# MainBoard.net
KiCad netlist of a schematic drawn in EAGLE
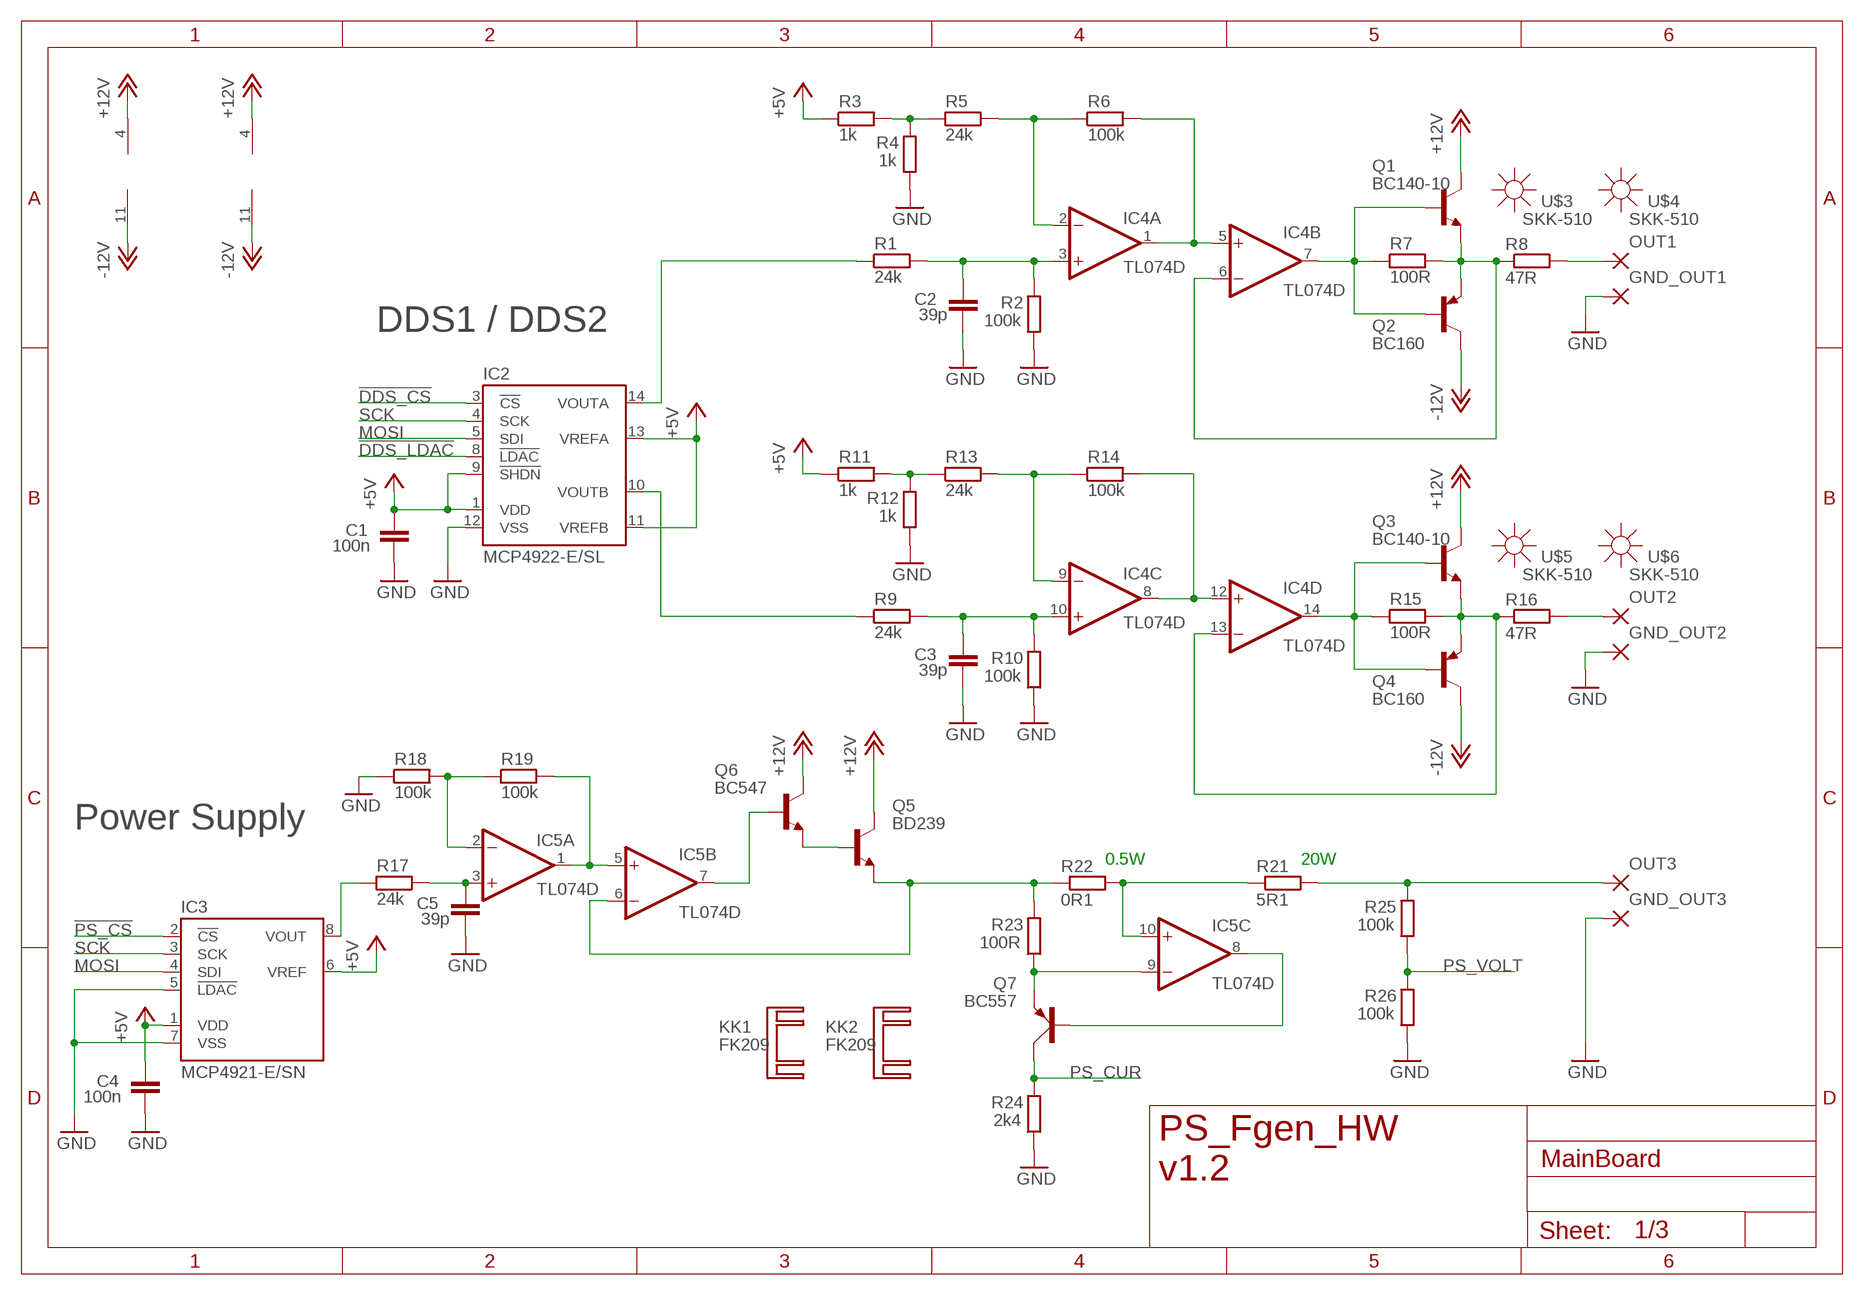
[diagram p0: schematic, sheet 1]
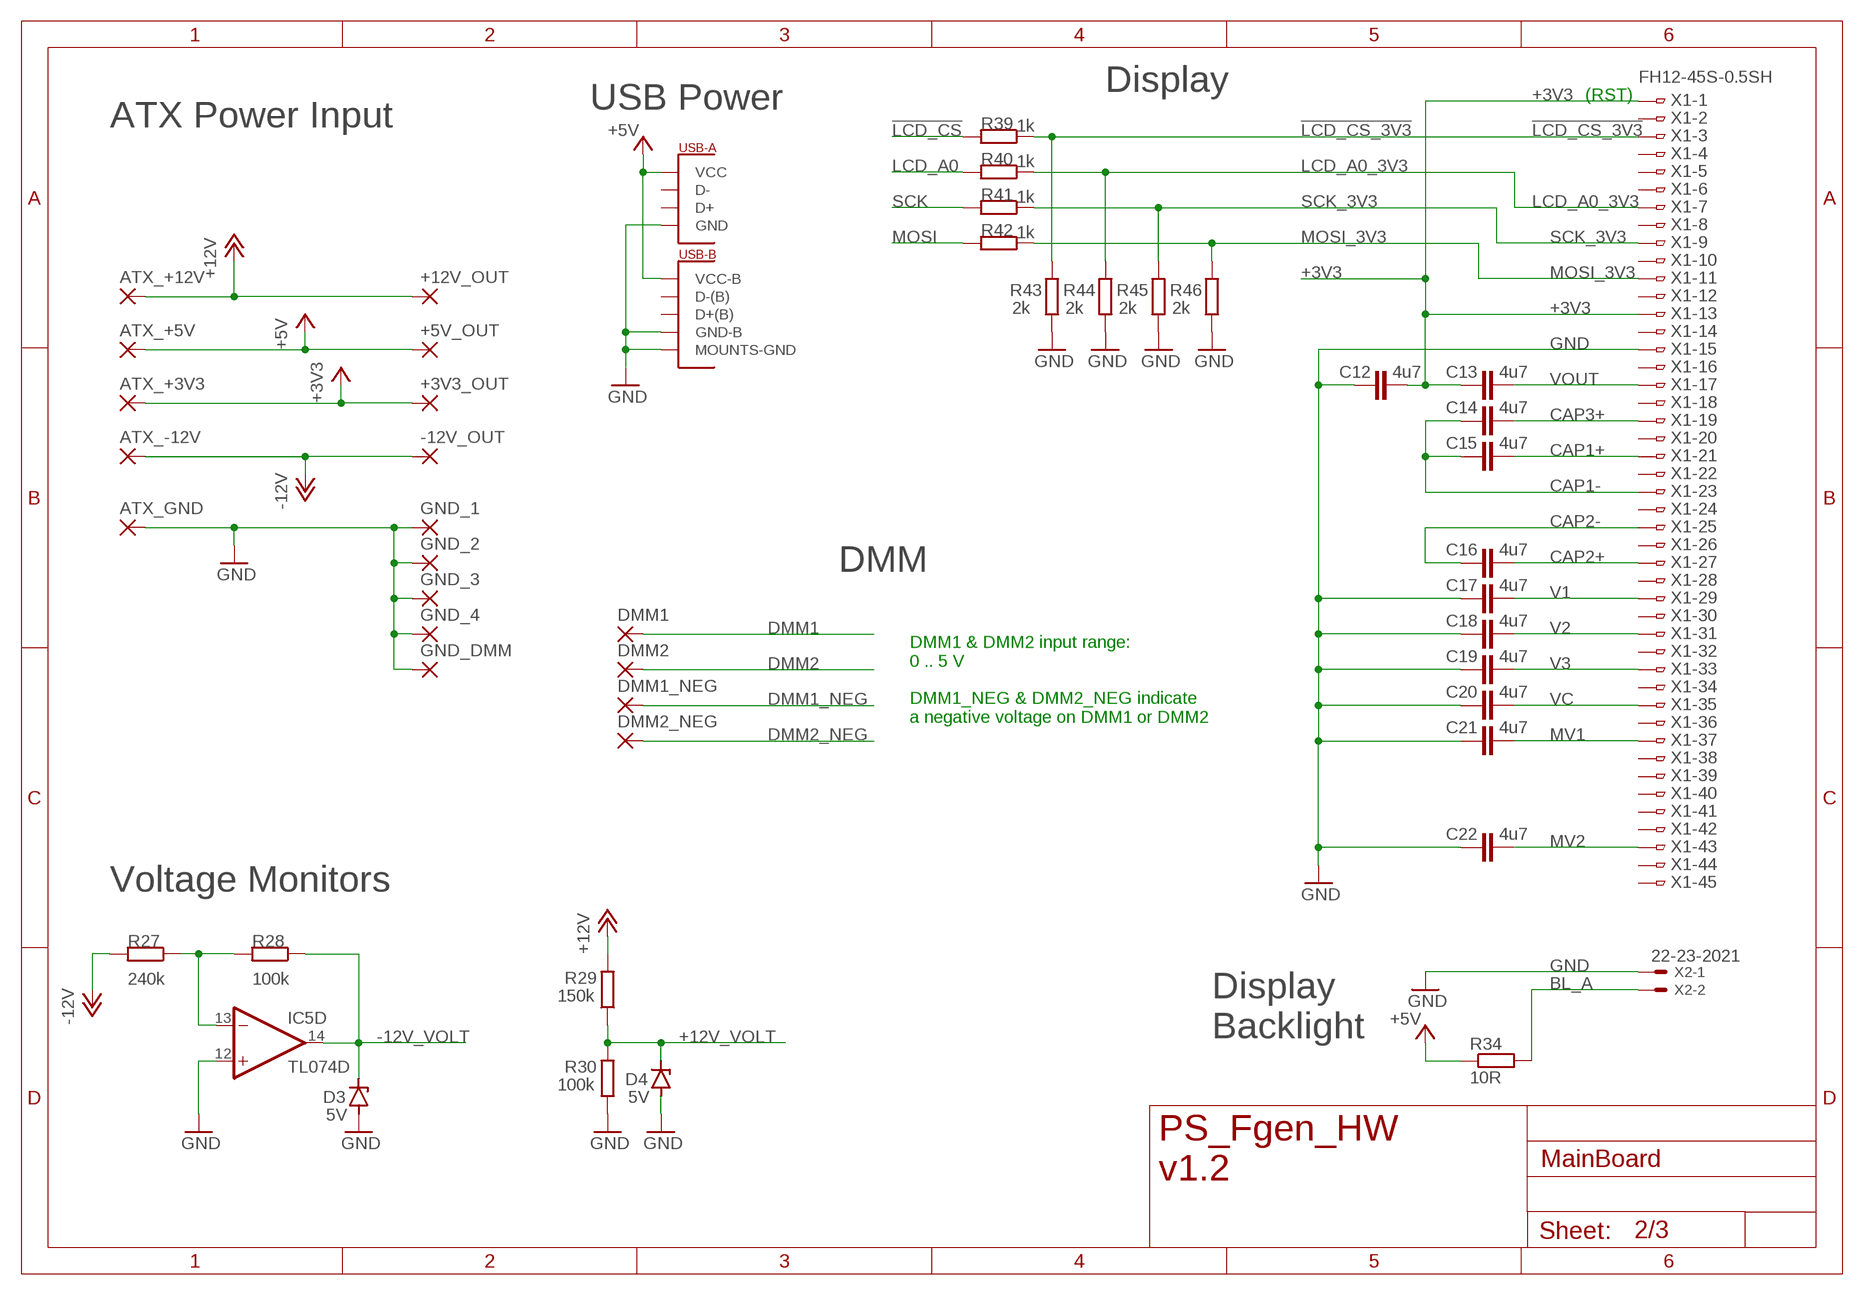
[diagram p1: schematic, sheet 2]
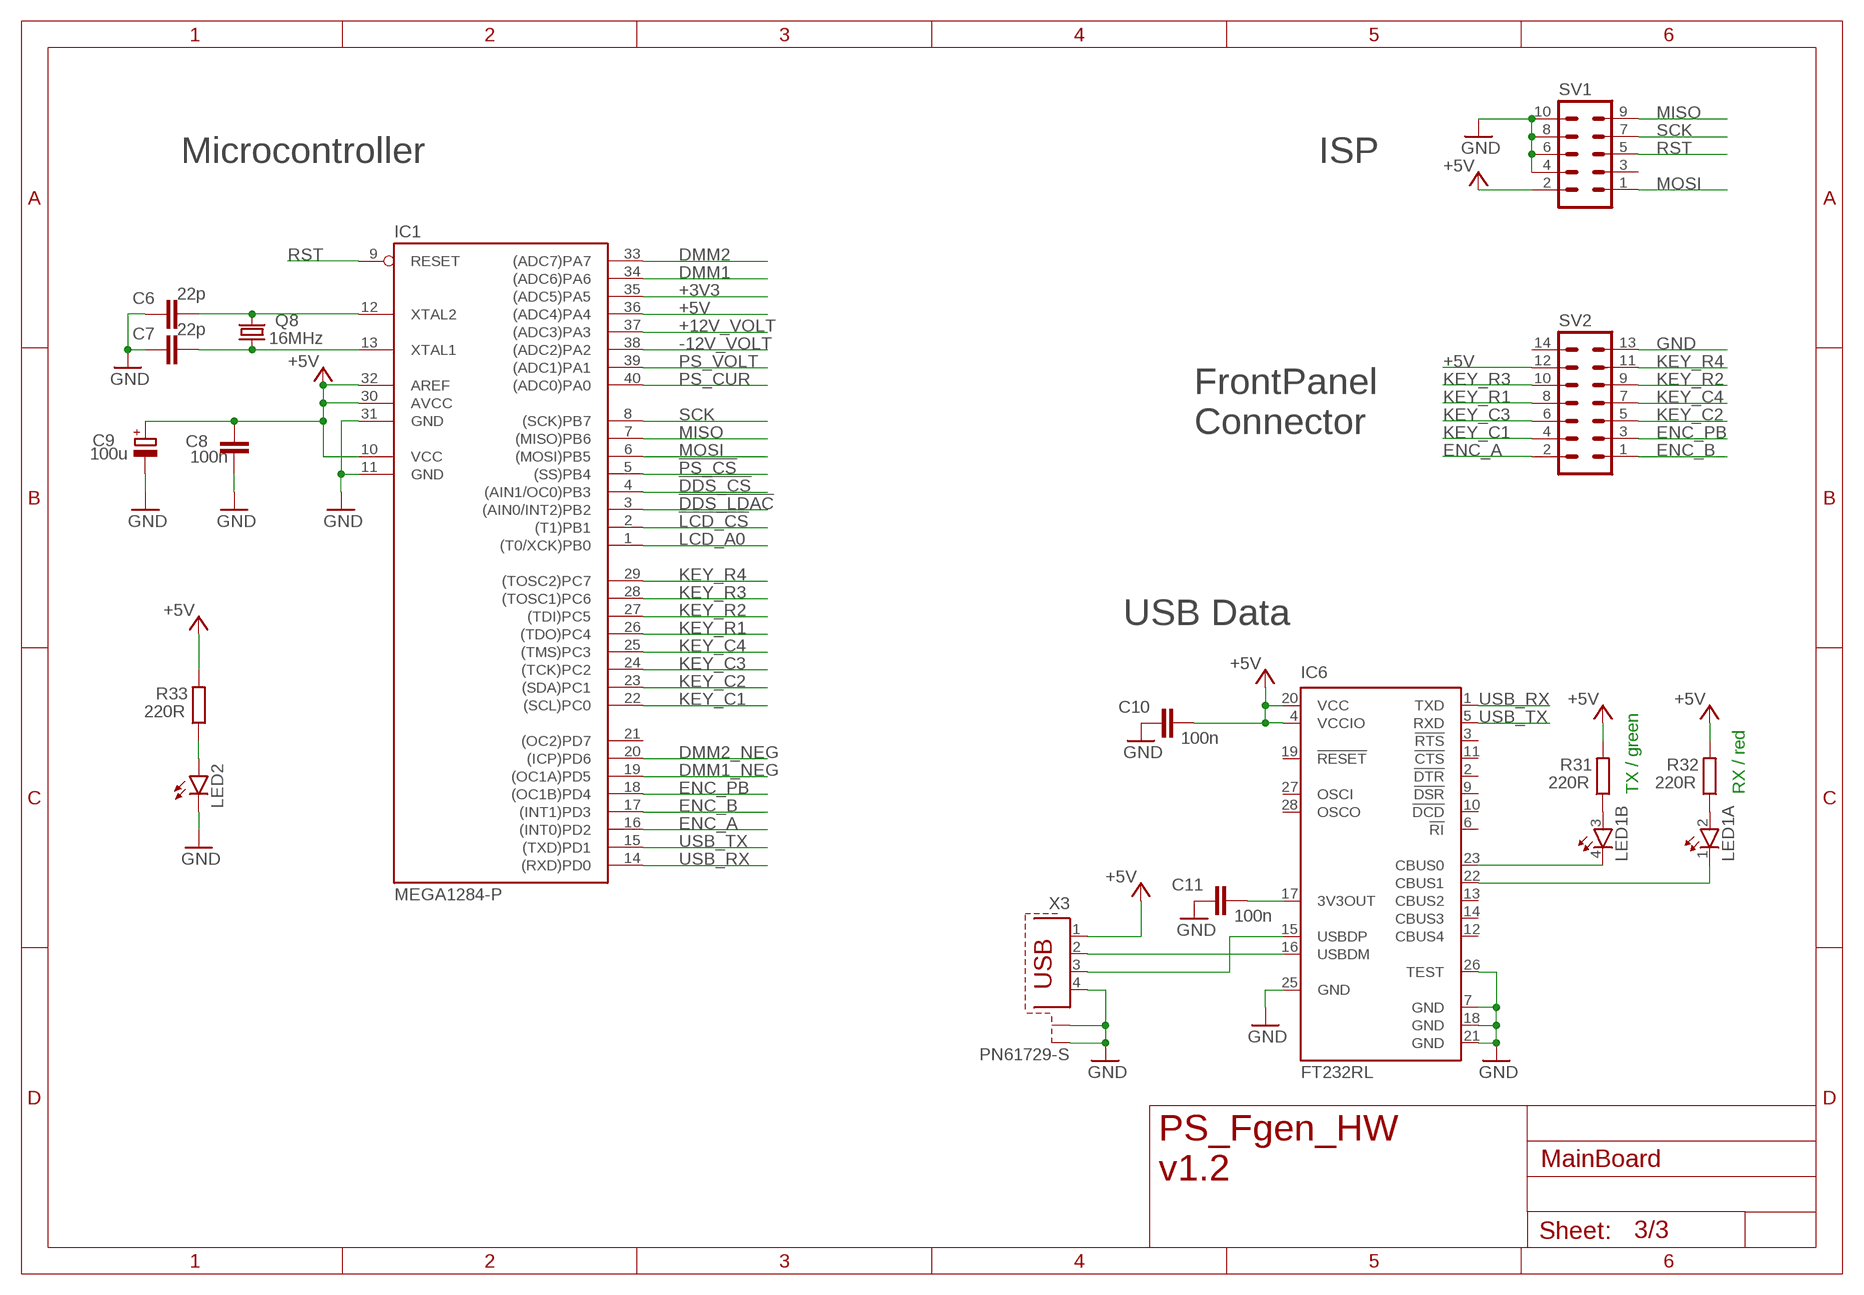
[diagram p2: schematic, sheet 3]

(export (version "E")
  (design (tool "Eeschema 10.0.6"))
  (components
    (comp (ref "C6")
      (value "22p")
      (footprint "eagle-import:C0805")
      (libsource (lib "eagle-import") (part "C-EUC0805"))
    )
    (comp (ref "C7")
      (value "22p")
      (footprint "eagle-import:C0805")
      (libsource (lib "eagle-import") (part "C-EUC0805"))
    )
    (comp (ref "C8")
      (value "100n")
      (footprint "eagle-import:C0805")
      (libsource (lib "eagle-import") (part "C-EUC0805"))
    )
    (comp (ref "C9")
      (value "100u")
      (footprint "eagle-import:PANASONIC_D")
      (libsource (lib "eagle-import") (part "CPOL-EUD"))
    )
    (comp (ref "C10")
      (value "100n")
      (footprint "eagle-import:C0805")
      (libsource (lib "eagle-import") (part "C-EUC0805"))
    )
    (comp (ref "C11")
      (value "100n")
      (footprint "eagle-import:C0805")
      (libsource (lib "eagle-import") (part "C-EUC0805"))
    )
    (comp (ref "IC1")
      (value "MEGA1284-P")
      (footprint "eagle-import:DIL40")
      (fields (field (name "MPN") "ATMEGA16-16PU"))
      (libsource (lib "eagle-import") (part "MEGA16-P"))
    )
    (comp (ref "IC6")
      (value "FT232RL")
      (footprint "eagle-import:SSOP28")
      (libsource (lib "eagle-import") (part "FT232RL"))
    )
    (comp (ref "LED1")
      (value "TOPLED-2--")
      (footprint "eagle-import:P-LCC-4-2")
      (libsource (lib "eagle-import") (part "TOPLED-2--"))
    )
    (comp (ref "LED2")
      (value "LEDCHIP-LED0805")
      (footprint "eagle-import:CHIP-LED0805")
      (libsource (lib "eagle-import") (part "LEDCHIP-LED0805"))
    )
    (comp (ref "Q8")
      (value "16MHz")
      (footprint "eagle-import:HC49_S")
      (libsource (lib "eagle-import") (part "CRYSTALHC49S"))
    )
    (comp (ref "R31")
      (value "220R")
      (footprint "eagle-import:R0805")
      (libsource (lib "eagle-import") (part "R-EU_R0805"))
    )
    (comp (ref "R32")
      (value "220R")
      (footprint "eagle-import:R0805")
      (libsource (lib "eagle-import") (part "R-EU_R0805"))
    )
    (comp (ref "R33")
      (value "220R")
      (footprint "eagle-import:R0805")
      (libsource (lib "eagle-import") (part "R-EU_R0805"))
    )
    (comp (ref "SV1")
      (value "ML10")
      (footprint "eagle-import:ML10")
      (libsource (lib "eagle-import") (part "ML10"))
    )
    (comp (ref "SV2")
      (value "ML14")
      (footprint "eagle-import:ML14")
      (libsource (lib "eagle-import") (part "ML14"))
    )
    (comp (ref "X3")
      (value "PN61729-S")
      (footprint "eagle-import:PN61729-S")
      (libsource (lib "eagle-import") (part "PN61729-S"))
    )
    (comp (ref "C1")
      (value "100n")
      (footprint "eagle-import:C0805")
      (libsource (lib "eagle-import") (part "C-EUC0805"))
    )
    (comp (ref "C2")
      (value "39p")
      (footprint "eagle-import:C0805")
      (libsource (lib "eagle-import") (part "C-EUC0805"))
    )
    (comp (ref "C3")
      (value "39p")
      (footprint "eagle-import:C0805")
      (libsource (lib "eagle-import") (part "C-EUC0805"))
    )
    (comp (ref "C4")
      (value "100n")
      (footprint "eagle-import:C0805")
      (libsource (lib "eagle-import") (part "C-EUC0805"))
    )
    (comp (ref "C5")
      (value "39p")
      (footprint "eagle-import:C0805")
      (libsource (lib "eagle-import") (part "C-EUC0805"))
    )
    (comp (ref "GND_OUT1")
      (value "2,54/1,0")
      (footprint "eagle-import:2,54_1,0")
      (libsource (lib "eagle-import") (part "2,54/1,0"))
    )
    (comp (ref "GND_OUT2")
      (value "2,54/1,0")
      (footprint "eagle-import:2,54_1,0")
      (libsource (lib "eagle-import") (part "2,54/1,0"))
    )
    (comp (ref "GND_OUT3")
      (value "2,54/1,0")
      (footprint "eagle-import:2,54_1,0")
      (libsource (lib "eagle-import") (part "2,54/1,0"))
    )
    (comp (ref "IC2")
      (value "MCP4922-E/SL")
      (footprint "eagle-import:SO14")
      (libsource (lib "eagle-import") (part "MCP4922-E/SL"))
    )
    (comp (ref "IC3")
      (value "MCP4921-E/SN")
      (footprint "eagle-import:SO08")
      (libsource (lib "eagle-import") (part "MCP4921-E/SN"))
    )
    (comp (ref "IC4")
      (value "TL074D")
      (footprint "eagle-import:SO14")
      (libsource (lib "eagle-import") (part "TL074D"))
    )
    (comp (ref "IC5")
      (value "TL074D")
      (footprint "eagle-import:SO14")
      (libsource (lib "eagle-import") (part "TL074D"))
    )
    (comp (ref "KK1")
      (value "FK209")
      (footprint "eagle-import:FK209")
      (libsource (lib "eagle-import") (part "FK209"))
    )
    (comp (ref "KK2")
      (value "FK209")
      (footprint "eagle-import:FK209")
      (libsource (lib "eagle-import") (part "FK209"))
    )
    (comp (ref "OUT1")
      (value "2,54/1,0")
      (footprint "eagle-import:2,54_1,0")
      (libsource (lib "eagle-import") (part "2,54/1,0"))
    )
    (comp (ref "OUT2")
      (value "2,54/1,0")
      (footprint "eagle-import:2,54_1,0")
      (libsource (lib "eagle-import") (part "2,54/1,0"))
    )
    (comp (ref "OUT3")
      (value "2,54/1,0")
      (footprint "eagle-import:2,54_1,0")
      (libsource (lib "eagle-import") (part "2,54/1,0"))
    )
    (comp (ref "Q1")
      (value "BC140-10")
      (footprint "eagle-import:TO39")
      (libsource (lib "eagle-import") (part "BC140-10"))
    )
    (comp (ref "Q2")
      (value "BC160")
      (footprint "eagle-import:TO39")
      (libsource (lib "eagle-import") (part "BC160"))
    )
    (comp (ref "Q3")
      (value "BC140-10")
      (footprint "eagle-import:TO39")
      (libsource (lib "eagle-import") (part "BC140-10"))
    )
    (comp (ref "Q4")
      (value "BC160")
      (footprint "eagle-import:TO39")
      (libsource (lib "eagle-import") (part "BC160"))
    )
    (comp (ref "Q5")
      (value "BD239")
      (footprint "eagle-import:CB-274")
      (libsource (lib "eagle-import") (part "BD239TO220BV"))
    )
    (comp (ref "Q6")
      (value "BC547")
      (footprint "eagle-import:TO92")
      (libsource (lib "eagle-import") (part "BC547"))
    )
    (comp (ref "Q7")
      (value "BC557")
      (footprint "eagle-import:SOT54A")
      (libsource (lib "eagle-import") (part "BC557"))
    )
    (comp (ref "R1")
      (value "24k")
      (footprint "eagle-import:R0805")
      (libsource (lib "eagle-import") (part "R-EU_R0805"))
    )
    (comp (ref "R2")
      (value "100k")
      (footprint "eagle-import:R0805")
      (libsource (lib "eagle-import") (part "R-EU_R0805"))
    )
    (comp (ref "R3")
      (value "1k")
      (footprint "eagle-import:R0805")
      (libsource (lib "eagle-import") (part "R-EU_R0805"))
    )
    (comp (ref "R4")
      (value "1k")
      (footprint "eagle-import:R0805")
      (libsource (lib "eagle-import") (part "R-EU_R0805"))
    )
    (comp (ref "R5")
      (value "24k")
      (footprint "eagle-import:R0805")
      (libsource (lib "eagle-import") (part "R-EU_R0805"))
    )
    (comp (ref "R6")
      (value "100k")
      (footprint "eagle-import:R0805")
      (libsource (lib "eagle-import") (part "R-EU_R0805"))
    )
    (comp (ref "R7")
      (value "100R")
      (footprint "eagle-import:R0805")
      (libsource (lib "eagle-import") (part "R-EU_R0805"))
    )
    (comp (ref "R8")
      (value "47R")
      (footprint "eagle-import:0411_15")
      (libsource (lib "eagle-import") (part "R-EU_0411/15"))
    )
    (comp (ref "R9")
      (value "24k")
      (footprint "eagle-import:R0805")
      (libsource (lib "eagle-import") (part "R-EU_R0805"))
    )
    (comp (ref "R10")
      (value "100k")
      (footprint "eagle-import:R0805")
      (libsource (lib "eagle-import") (part "R-EU_R0805"))
    )
    (comp (ref "R11")
      (value "1k")
      (footprint "eagle-import:R0805")
      (libsource (lib "eagle-import") (part "R-EU_R0805"))
    )
    (comp (ref "R12")
      (value "1k")
      (footprint "eagle-import:R0805")
      (libsource (lib "eagle-import") (part "R-EU_R0805"))
    )
    (comp (ref "R13")
      (value "24k")
      (footprint "eagle-import:R0805")
      (libsource (lib "eagle-import") (part "R-EU_R0805"))
    )
    (comp (ref "R14")
      (value "100k")
      (footprint "eagle-import:R0805")
      (libsource (lib "eagle-import") (part "R-EU_R0805"))
    )
    (comp (ref "R15")
      (value "100R")
      (footprint "eagle-import:R0805")
      (libsource (lib "eagle-import") (part "R-EU_R0805"))
    )
    (comp (ref "R16")
      (value "47R")
      (footprint "eagle-import:0411_15")
      (libsource (lib "eagle-import") (part "R-EU_0411/15"))
    )
    (comp (ref "R17")
      (value "24k")
      (footprint "eagle-import:R0805")
      (libsource (lib "eagle-import") (part "R-EU_R0805"))
    )
    (comp (ref "R18")
      (value "100k")
      (footprint "eagle-import:R0805")
      (libsource (lib "eagle-import") (part "R-EU_R0805"))
    )
    (comp (ref "R19")
      (value "100k")
      (footprint "eagle-import:R0805")
      (libsource (lib "eagle-import") (part "R-EU_R0805"))
    )
    (comp (ref "R21")
      (value "5R1")
      (footprint "eagle-import:0411_15")
      (libsource (lib "eagle-import") (part "R-EU_0411/15"))
    )
    (comp (ref "R22")
      (value "0R1")
      (footprint "eagle-import:0411_15")
      (libsource (lib "eagle-import") (part "R-EU_0411/15"))
    )
    (comp (ref "R23")
      (value "100R")
      (footprint "eagle-import:R0805")
      (libsource (lib "eagle-import") (part "R-EU_R0805"))
    )
    (comp (ref "R24")
      (value "2k4")
      (footprint "eagle-import:R0805")
      (libsource (lib "eagle-import") (part "R-EU_R0805"))
    )
    (comp (ref "R25")
      (value "100k")
      (footprint "eagle-import:R0805")
      (libsource (lib "eagle-import") (part "R-EU_R0805"))
    )
    (comp (ref "R26")
      (value "100k")
      (footprint "eagle-import:R0805")
      (libsource (lib "eagle-import") (part "R-EU_R0805"))
    )
    (comp (ref "U$3")
      (value "SKK-510")
      (footprint "eagle-import:SKK")
      (libsource (lib "eagle-import") (part "SKK-510"))
    )
    (comp (ref "U$4")
      (value "SKK-510")
      (footprint "eagle-import:SKK")
      (libsource (lib "eagle-import") (part "SKK-510"))
    )
    (comp (ref "U$5")
      (value "SKK-510")
      (footprint "eagle-import:SKK")
      (libsource (lib "eagle-import") (part "SKK-510"))
    )
    (comp (ref "U$6")
      (value "SKK-510")
      (footprint "eagle-import:SKK")
      (libsource (lib "eagle-import") (part "SKK-510"))
    )
    (comp (ref "+3V3_OUT")
      (value "2,54/1,0")
      (footprint "eagle-import:2,54_1,0")
      (libsource (lib "eagle-import") (part "2,54/1,0"))
    )
    (comp (ref "+5V_OUT")
      (value "2,54/1,0")
      (footprint "eagle-import:2,54_1,0")
      (libsource (lib "eagle-import") (part "2,54/1,0"))
    )
    (comp (ref "+12V_OUT")
      (value "2,54/1,0")
      (footprint "eagle-import:2,54_1,0")
      (libsource (lib "eagle-import") (part "2,54/1,0"))
    )
    (comp (ref "-12V_OUT")
      (value "2,54/1,0")
      (footprint "eagle-import:2,54_1,0")
      (libsource (lib "eagle-import") (part "2,54/1,0"))
    )
    (comp (ref "ATX_+3V3")
      (value "2,54/1,0")
      (footprint "eagle-import:2,54_1,0")
      (libsource (lib "eagle-import") (part "2,54/1,0"))
    )
    (comp (ref "ATX_+5V")
      (value "2,54/1,0")
      (footprint "eagle-import:2,54_1,0")
      (libsource (lib "eagle-import") (part "2,54/1,0"))
    )
    (comp (ref "ATX_+12V")
      (value "2,54/1,0")
      (footprint "eagle-import:2,54_1,0")
      (libsource (lib "eagle-import") (part "2,54/1,0"))
    )
    (comp (ref "ATX_-12V")
      (value "2,54/1,0")
      (footprint "eagle-import:2,54_1,0")
      (libsource (lib "eagle-import") (part "2,54/1,0"))
    )
    (comp (ref "ATX_GND")
      (value "2,54/1,0")
      (footprint "eagle-import:2,54_1,0")
      (libsource (lib "eagle-import") (part "2,54/1,0"))
    )
    (comp (ref "C12")
      (value "4u7")
      (footprint "eagle-import:C0805")
      (libsource (lib "eagle-import") (part "C-EUC0805"))
    )
    (comp (ref "C13")
      (value "4u7")
      (footprint "eagle-import:C0805")
      (libsource (lib "eagle-import") (part "C-EUC0805"))
    )
    (comp (ref "C14")
      (value "4u7")
      (footprint "eagle-import:C0805")
      (libsource (lib "eagle-import") (part "C-EUC0805"))
    )
    (comp (ref "C15")
      (value "4u7")
      (footprint "eagle-import:C0805")
      (libsource (lib "eagle-import") (part "C-EUC0805"))
    )
    (comp (ref "C16")
      (value "4u7")
      (footprint "eagle-import:C0805")
      (libsource (lib "eagle-import") (part "C-EUC0805"))
    )
    (comp (ref "C17")
      (value "4u7")
      (footprint "eagle-import:C0805")
      (libsource (lib "eagle-import") (part "C-EUC0805"))
    )
    (comp (ref "C18")
      (value "4u7")
      (footprint "eagle-import:C0805")
      (libsource (lib "eagle-import") (part "C-EUC0805"))
    )
    (comp (ref "C19")
      (value "4u7")
      (footprint "eagle-import:C0805")
      (libsource (lib "eagle-import") (part "C-EUC0805"))
    )
    (comp (ref "C20")
      (value "4u7")
      (footprint "eagle-import:C0805")
      (libsource (lib "eagle-import") (part "C-EUC0805"))
    )
    (comp (ref "C21")
      (value "4u7")
      (footprint "eagle-import:C0805")
      (libsource (lib "eagle-import") (part "C-EUC0805"))
    )
    (comp (ref "C22")
      (value "4u7")
      (footprint "eagle-import:C0805")
      (libsource (lib "eagle-import") (part "C-EUC0805"))
    )
    (comp (ref "D3")
      (value "5V")
      (footprint "eagle-import:SOD80C")
      (libsource (lib "eagle-import") (part "ZENER-DIODESOD80C"))
    )
    (comp (ref "D4")
      (value "5V")
      (footprint "eagle-import:SOD80C")
      (libsource (lib "eagle-import") (part "ZENER-DIODESOD80C"))
    )
    (comp (ref "DMM1")
      (value "2,54/1,0")
      (footprint "eagle-import:2,54_1,0")
      (libsource (lib "eagle-import") (part "2,54/1,0"))
    )
    (comp (ref "DMM1_NEG")
      (value "2,54/1,0")
      (footprint "eagle-import:2,54_1,0")
      (libsource (lib "eagle-import") (part "2,54/1,0"))
    )
    (comp (ref "DMM2")
      (value "2,54/1,0")
      (footprint "eagle-import:2,54_1,0")
      (libsource (lib "eagle-import") (part "2,54/1,0"))
    )
    (comp (ref "DMM2_NEG")
      (value "2,54/1,0")
      (footprint "eagle-import:2,54_1,0")
      (libsource (lib "eagle-import") (part "2,54/1,0"))
    )
    (comp (ref "GND_1")
      (value "2,54/1,0")
      (footprint "eagle-import:2,54_1,0")
      (libsource (lib "eagle-import") (part "2,54/1,0"))
    )
    (comp (ref "GND_2")
      (value "2,54/1,0")
      (footprint "eagle-import:2,54_1,0")
      (libsource (lib "eagle-import") (part "2,54/1,0"))
    )
    (comp (ref "GND_3")
      (value "2,54/1,0")
      (footprint "eagle-import:2,54_1,0")
      (libsource (lib "eagle-import") (part "2,54/1,0"))
    )
    (comp (ref "GND_4")
      (value "2,54/1,0")
      (footprint "eagle-import:2,54_1,0")
      (libsource (lib "eagle-import") (part "2,54/1,0"))
    )
    (comp (ref "GND_DMM")
      (value "2,54/1,0")
      (footprint "eagle-import:2,54_1,0")
      (libsource (lib "eagle-import") (part "2,54/1,0"))
    )
    (comp (ref "R27")
      (value "240k")
      (footprint "eagle-import:R0805")
      (libsource (lib "eagle-import") (part "R-EU_R0805"))
    )
    (comp (ref "R28")
      (value "100k")
      (footprint "eagle-import:R0805")
      (libsource (lib "eagle-import") (part "R-EU_R0805"))
    )
    (comp (ref "R29")
      (value "150k")
      (footprint "eagle-import:R0805")
      (libsource (lib "eagle-import") (part "R-EU_R0805"))
    )
    (comp (ref "R30")
      (value "100k")
      (footprint "eagle-import:R0805")
      (libsource (lib "eagle-import") (part "R-EU_R0805"))
    )
    (comp (ref "R34")
      (value "10R")
      (footprint "eagle-import:R0805")
      (libsource (lib "eagle-import") (part "rcl_334_R-EU_R0805"))
    )
    (comp (ref "R39")
      (value "1k")
      (footprint "eagle-import:R0805")
      (libsource (lib "eagle-import") (part "R-EU_R0805"))
    )
    (comp (ref "R40")
      (value "1k")
      (footprint "eagle-import:R0805")
      (libsource (lib "eagle-import") (part "R-EU_R0805"))
    )
    (comp (ref "R41")
      (value "1k")
      (footprint "eagle-import:R0805")
      (libsource (lib "eagle-import") (part "R-EU_R0805"))
    )
    (comp (ref "R42")
      (value "1k")
      (footprint "eagle-import:R0805")
      (libsource (lib "eagle-import") (part "R-EU_R0805"))
    )
    (comp (ref "R43")
      (value "2k")
      (footprint "eagle-import:R0805")
      (libsource (lib "eagle-import") (part "R-EU_R0805"))
    )
    (comp (ref "R44")
      (value "2k")
      (footprint "eagle-import:R0805")
      (libsource (lib "eagle-import") (part "R-EU_R0805"))
    )
    (comp (ref "R45")
      (value "2k")
      (footprint "eagle-import:R0805")
      (libsource (lib "eagle-import") (part "R-EU_R0805"))
    )
    (comp (ref "R46")
      (value "2k")
      (footprint "eagle-import:R0805")
      (libsource (lib "eagle-import") (part "R-EU_R0805"))
    )
    (comp (ref "U$2")
      (value "DUAL-PORT-USB-REC")
      (footprint "eagle-import:DUAL-PORT-USB")
      (libsource (lib "eagle-import") (part "DUAL-PORT-USB-REC"))
    )
    (comp (ref "X1")
      (value "FH12-45S-0.5SH")
      (footprint "eagle-import:FH12-45S-0.5SH")
      (libsource (lib "eagle-import") (part "FH12-45S-0.5SH"))
    )
    (comp (ref "X2")
      (value "22-23-2021")
      (footprint "eagle-import:22-23-2021")
      (fields (field (name "MF") "MOLEX"))
      (libsource (lib "eagle-import") (part "22-23-2021"))
    )
  )
  (nets
    (net (code "1") (name "+3V3") (class "Default")
      (node (ref "+3V3_OUT") (pin "1") (pinfunction "P_1") (pintype "passive"))
      (node (ref "ATX_+3V3") (pin "1") (pinfunction "P_1") (pintype "passive"))
      (node (ref "C12") (pin "1") (pinfunction "1_1") (pintype "passive"))
      (node (ref "C13") (pin "2") (pinfunction "2_2") (pintype "passive"))
      (node (ref "IC1") (pin "35") (pinfunction "(ADC5)PA5_35") (pintype "bidirectional"))
      (node (ref "X1") (pin "1") (pinfunction "1_1") (pintype "passive"))
      (node (ref "X1") (pin "13") (pinfunction "1_13") (pintype "passive"))
    )
    (net (code "2") (name "+5V") (class "Default")
      (node (ref "+5V_OUT") (pin "1") (pinfunction "P_1") (pintype "passive"))
      (node (ref "ATX_+5V") (pin "1") (pinfunction "P_1") (pintype "passive"))
      (node (ref "C1") (pin "2") (pinfunction "2_2") (pintype "passive"))
      (node (ref "C10") (pin "1") (pinfunction "1_1") (pintype "passive"))
      (node (ref "C4") (pin "2") (pinfunction "2_2") (pintype "passive"))
      (node (ref "C8") (pin "2") (pinfunction "2_2") (pintype "passive"))
      (node (ref "C9") (pin "+") (pinfunction "+_+") (pintype "passive"))
      (node (ref "IC1") (pin "10") (pinfunction "VCC_10") (pintype "power_in"))
      (node (ref "IC1") (pin "30") (pinfunction "AVCC_30") (pintype "power_in"))
      (node (ref "IC1") (pin "32") (pinfunction "AREF_32") (pintype "passive"))
      (node (ref "IC1") (pin "36") (pinfunction "(ADC4)PA4_36") (pintype "bidirectional"))
      (node (ref "IC2") (pin "1") (pinfunction "VDD_1") (pintype "power_in"))
      (node (ref "IC2") (pin "11") (pinfunction "VREFB_11") (pintype "input"))
      (node (ref "IC2") (pin "13") (pinfunction "VREFA_13") (pintype "input"))
      (node (ref "IC2") (pin "9") (pinfunction "~{SHDN}_9") (pintype "input"))
      (node (ref "IC3") (pin "1") (pinfunction "VDD_1") (pintype "power_in"))
      (node (ref "IC3") (pin "6") (pinfunction "VREF_6") (pintype "input"))
      (node (ref "IC6") (pin "20") (pinfunction "VCC_20") (pintype "power_in"))
      (node (ref "IC6") (pin "4") (pinfunction "VCCIO_4") (pintype "power_in"))
      (node (ref "R11") (pin "1") (pinfunction "1_1") (pintype "passive"))
      (node (ref "R3") (pin "1") (pinfunction "1_1") (pintype "passive"))
      (node (ref "R31") (pin "2") (pinfunction "2_2") (pintype "passive"))
      (node (ref "R32") (pin "2") (pinfunction "2_2") (pintype "passive"))
      (node (ref "R33") (pin "2") (pinfunction "2_2") (pintype "passive"))
      (node (ref "R34") (pin "1") (pinfunction "1_1") (pintype "passive"))
      (node (ref "SV1") (pin "2") (pinfunction "2_2") (pintype "passive"))
      (node (ref "SV2") (pin "12") (pinfunction "12_12") (pintype "passive"))
      (node (ref "U$2") (pin "P$10") (pinfunction "VCC-B_P$10") (pintype "power_in"))
      (node (ref "U$2") (pin "P$12") (pinfunction "VCC_P$12") (pintype "power_in"))
      (node (ref "X3") (pin "1") (pinfunction "1_1") (pintype "passive"))
    )
    (net (code "3") (name "+12V") (class "Default")
      (node (ref "+12V_OUT") (pin "1") (pinfunction "P_1") (pintype "passive"))
      (node (ref "ATX_+12V") (pin "1") (pinfunction "P_1") (pintype "passive"))
      (node (ref "IC4") (pin "4") (pinfunction "V+_4") (pintype "power_in"))
      (node (ref "IC5") (pin "4") (pinfunction "V+_4") (pintype "power_in"))
      (node (ref "Q1") (pin "3") (pinfunction "C_3") (pintype "passive"))
      (node (ref "Q3") (pin "3") (pinfunction "C_3") (pintype "passive"))
      (node (ref "Q5") (pin "T2") (pinfunction "C_T2") (pintype "passive"))
      (node (ref "Q6") (pin "3") (pinfunction "C_3") (pintype "passive"))
      (node (ref "R29") (pin "2") (pinfunction "2_2") (pintype "passive"))
    )
    (net (code "4") (name "+12V_VOLT") (class "Default")
      (node (ref "D4") (pin "C") (pinfunction "C_C") (pintype "passive"))
      (node (ref "IC1") (pin "37") (pinfunction "(ADC3)PA3_37") (pintype "bidirectional"))
      (node (ref "R29") (pin "1") (pinfunction "1_1") (pintype "passive"))
      (node (ref "R30") (pin "2") (pinfunction "2_2") (pintype "passive"))
    )
    (net (code "5") (name "-12V") (class "Default")
      (node (ref "-12V_OUT") (pin "1") (pinfunction "P_1") (pintype "passive"))
      (node (ref "ATX_-12V") (pin "1") (pinfunction "P_1") (pintype "passive"))
      (node (ref "IC4") (pin "11") (pinfunction "V-_11") (pintype "power_in"))
      (node (ref "IC5") (pin "11") (pinfunction "V-_11") (pintype "power_in"))
      (node (ref "Q2") (pin "3") (pinfunction "C_3") (pintype "passive"))
      (node (ref "Q4") (pin "3") (pinfunction "C_3") (pintype "passive"))
      (node (ref "R27") (pin "2") (pinfunction "2_2") (pintype "passive"))
    )
    (net (code "6") (name "-12V_VOLT") (class "Default")
      (node (ref "D3") (pin "C") (pinfunction "C_C") (pintype "passive"))
      (node (ref "IC1") (pin "38") (pinfunction "(ADC2)PA2_38") (pintype "bidirectional"))
      (node (ref "IC5") (pin "14") (pinfunction "OUT_14") (pintype "output"))
      (node (ref "R28") (pin "1") (pinfunction "1_1") (pintype "passive"))
    )
    (net (code "7") (name "BL_A") (class "Default")
      (node (ref "R34") (pin "2") (pinfunction "2_2") (pintype "passive"))
      (node (ref "X2") (pin "2") (pinfunction "S_2") (pintype "passive"))
    )
    (net (code "8") (name "CAP1+") (class "Default")
      (node (ref "C15") (pin "1") (pinfunction "1_1") (pintype "passive"))
      (node (ref "X1") (pin "21") (pinfunction "1_21") (pintype "passive"))
    )
    (net (code "9") (name "CAP1-") (class "Default")
      (node (ref "C14") (pin "2") (pinfunction "2_2") (pintype "passive"))
      (node (ref "C15") (pin "2") (pinfunction "2_2") (pintype "passive"))
      (node (ref "X1") (pin "23") (pinfunction "1_23") (pintype "passive"))
    )
    (net (code "10") (name "CAP2+") (class "Default")
      (node (ref "C16") (pin "1") (pinfunction "1_1") (pintype "passive"))
      (node (ref "X1") (pin "27") (pinfunction "1_27") (pintype "passive"))
    )
    (net (code "11") (name "CAP2-") (class "Default")
      (node (ref "C16") (pin "2") (pinfunction "2_2") (pintype "passive"))
      (node (ref "X1") (pin "25") (pinfunction "1_25") (pintype "passive"))
    )
    (net (code "12") (name "CAP3+") (class "Default")
      (node (ref "C14") (pin "1") (pinfunction "1_1") (pintype "passive"))
      (node (ref "X1") (pin "19") (pinfunction "1_19") (pintype "passive"))
    )
    (net (code "13") (name "DMM1") (class "Default")
      (node (ref "DMM1") (pin "1") (pinfunction "P_1") (pintype "passive"))
      (node (ref "IC1") (pin "34") (pinfunction "(ADC6)PA6_34") (pintype "bidirectional"))
    )
    (net (code "14") (name "DMM1_NEG") (class "Default")
      (node (ref "DMM1_NEG") (pin "1") (pinfunction "P_1") (pintype "passive"))
      (node (ref "IC1") (pin "19") (pinfunction "(OC1A)PD5_19") (pintype "bidirectional"))
    )
    (net (code "15") (name "DMM2") (class "Default")
      (node (ref "DMM2") (pin "1") (pinfunction "P_1") (pintype "passive"))
      (node (ref "IC1") (pin "33") (pinfunction "(ADC7)PA7_33") (pintype "bidirectional"))
    )
    (net (code "16") (name "DMM2_NEG") (class "Default")
      (node (ref "DMM2_NEG") (pin "1") (pinfunction "P_1") (pintype "passive"))
      (node (ref "IC1") (pin "20") (pinfunction "(ICP)PD6_20") (pintype "bidirectional"))
    )
    (net (code "17") (name "ENC_A") (class "Default")
      (node (ref "IC1") (pin "16") (pinfunction "(INT0)PD2_16") (pintype "bidirectional"))
      (node (ref "SV2") (pin "2") (pinfunction "2_2") (pintype "passive"))
    )
    (net (code "18") (name "ENC_B") (class "Default")
      (node (ref "IC1") (pin "17") (pinfunction "(INT1)PD3_17") (pintype "bidirectional"))
      (node (ref "SV2") (pin "1") (pinfunction "1_1") (pintype "passive"))
    )
    (net (code "19") (name "ENC_PB") (class "Default")
      (node (ref "IC1") (pin "18") (pinfunction "(OC1B)PD4_18") (pintype "bidirectional"))
      (node (ref "SV2") (pin "3") (pinfunction "3_3") (pintype "passive"))
    )
    (net (code "20") (name "GND") (class "Default")
      (node (ref "ATX_GND") (pin "1") (pinfunction "P_1") (pintype "passive"))
      (node (ref "C1") (pin "1") (pinfunction "1_1") (pintype "passive"))
      (node (ref "C10") (pin "2") (pinfunction "2_2") (pintype "passive"))
      (node (ref "C11") (pin "2") (pinfunction "2_2") (pintype "passive"))
      (node (ref "C12") (pin "2") (pinfunction "2_2") (pintype "passive"))
      (node (ref "C17") (pin "2") (pinfunction "2_2") (pintype "passive"))
      (node (ref "C18") (pin "2") (pinfunction "2_2") (pintype "passive"))
      (node (ref "C19") (pin "2") (pinfunction "2_2") (pintype "passive"))
      (node (ref "C2") (pin "1") (pinfunction "1_1") (pintype "passive"))
      (node (ref "C20") (pin "2") (pinfunction "2_2") (pintype "passive"))
      (node (ref "C21") (pin "2") (pinfunction "2_2") (pintype "passive"))
      (node (ref "C22") (pin "2") (pinfunction "2_2") (pintype "passive"))
      (node (ref "C3") (pin "1") (pinfunction "1_1") (pintype "passive"))
      (node (ref "C4") (pin "1") (pinfunction "1_1") (pintype "passive"))
      (node (ref "C5") (pin "1") (pinfunction "1_1") (pintype "passive"))
      (node (ref "C6") (pin "2") (pinfunction "2_2") (pintype "passive"))
      (node (ref "C7") (pin "2") (pinfunction "2_2") (pintype "passive"))
      (node (ref "C8") (pin "1") (pinfunction "1_1") (pintype "passive"))
      (node (ref "C9") (pin "-") (pinfunction "-_-") (pintype "passive"))
      (node (ref "D3") (pin "A") (pinfunction "A_A") (pintype "passive"))
      (node (ref "D4") (pin "A") (pinfunction "A_A") (pintype "passive"))
      (node (ref "GND_1") (pin "1") (pinfunction "P_1") (pintype "passive"))
      (node (ref "GND_2") (pin "1") (pinfunction "P_1") (pintype "passive"))
      (node (ref "GND_3") (pin "1") (pinfunction "P_1") (pintype "passive"))
      (node (ref "GND_4") (pin "1") (pinfunction "P_1") (pintype "passive"))
      (node (ref "GND_DMM") (pin "1") (pinfunction "P_1") (pintype "passive"))
      (node (ref "GND_OUT1") (pin "1") (pinfunction "P_1") (pintype "passive"))
      (node (ref "GND_OUT2") (pin "1") (pinfunction "P_1") (pintype "passive"))
      (node (ref "GND_OUT3") (pin "1") (pinfunction "P_1") (pintype "passive"))
      (node (ref "IC1") (pin "11") (pinfunction "GND_11") (pintype "power_in"))
      (node (ref "IC1") (pin "31") (pinfunction "GND_31") (pintype "power_in"))
      (node (ref "IC2") (pin "12") (pinfunction "VSS_12") (pintype "power_in"))
      (node (ref "IC3") (pin "5") (pinfunction "~{LDAC}_5") (pintype "input"))
      (node (ref "IC3") (pin "7") (pinfunction "VSS_7") (pintype "power_in"))
      (node (ref "IC5") (pin "12") (pinfunction "+IN_12") (pintype "input"))
      (node (ref "IC6") (pin "18") (pinfunction "GND_18") (pintype "power_in"))
      (node (ref "IC6") (pin "21") (pinfunction "GND_21") (pintype "power_in"))
      (node (ref "IC6") (pin "25") (pinfunction "GND_25") (pintype "power_in"))
      (node (ref "IC6") (pin "26") (pinfunction "TEST_26") (pintype "input"))
      (node (ref "IC6") (pin "7") (pinfunction "GND_7") (pintype "power_in"))
      (node (ref "LED2") (pin "C") (pinfunction "C_C") (pintype "passive"))
      (node (ref "R10") (pin "1") (pinfunction "1_1") (pintype "passive"))
      (node (ref "R12") (pin "1") (pinfunction "1_1") (pintype "passive"))
      (node (ref "R18") (pin "1") (pinfunction "1_1") (pintype "passive"))
      (node (ref "R2") (pin "1") (pinfunction "1_1") (pintype "passive"))
      (node (ref "R24") (pin "1") (pinfunction "1_1") (pintype "passive"))
      (node (ref "R26") (pin "1") (pinfunction "1_1") (pintype "passive"))
      (node (ref "R30") (pin "1") (pinfunction "1_1") (pintype "passive"))
      (node (ref "R4") (pin "1") (pinfunction "1_1") (pintype "passive"))
      (node (ref "R43") (pin "2") (pinfunction "2_2") (pintype "passive"))
      (node (ref "R44") (pin "2") (pinfunction "2_2") (pintype "passive"))
      (node (ref "R45") (pin "2") (pinfunction "2_2") (pintype "passive"))
      (node (ref "R46") (pin "2") (pinfunction "2_2") (pintype "passive"))
      (node (ref "SV1") (pin "10") (pinfunction "10_10") (pintype "passive"))
      (node (ref "SV1") (pin "4") (pinfunction "4_4") (pintype "passive"))
      (node (ref "SV1") (pin "6") (pinfunction "6_6") (pintype "passive"))
      (node (ref "SV1") (pin "8") (pinfunction "8_8") (pintype "passive"))
      (node (ref "SV2") (pin "13") (pinfunction "13_13") (pintype "passive"))
      (node (ref "U$2") (pin "GND") (pinfunction "MOUNTS-GND_GND") (pintype "power_in"))
      (node (ref "U$2") (pin "P$11") (pinfunction "GND_P$11") (pintype "power_in"))
      (node (ref "U$2") (pin "P$2") (pinfunction "MOUNTS-GND_P$2") (pintype "power_in"))
      (node (ref "U$2") (pin "P$3") (pinfunction "MOUNTS-GND_P$3") (pintype "power_in"))
      (node (ref "U$2") (pin "P$4") (pinfunction "MOUNTS-GND_P$4") (pintype "power_in"))
      (node (ref "U$2") (pin "P$9") (pinfunction "GND-B_P$9") (pintype "power_in"))
      (node (ref "X1") (pin "15") (pinfunction "1_15") (pintype "passive"))
      (node (ref "X2") (pin "1") (pinfunction "S_1") (pintype "passive"))
      (node (ref "X3") (pin "4") (pinfunction "4_4") (pintype "passive"))
      (node (ref "X3") (pin "S1") (pinfunction "S1_S1") (pintype "passive"))
      (node (ref "X3") (pin "S2") (pinfunction "S2_S2") (pintype "passive"))
    )
    (net (code "21") (name "KEY_C1") (class "Default")
      (node (ref "IC1") (pin "22") (pinfunction "(SCL)PC0_22") (pintype "bidirectional"))
      (node (ref "SV2") (pin "4") (pinfunction "4_4") (pintype "passive"))
    )
    (net (code "22") (name "KEY_C2") (class "Default")
      (node (ref "IC1") (pin "23") (pinfunction "(SDA)PC1_23") (pintype "bidirectional"))
      (node (ref "SV2") (pin "5") (pinfunction "5_5") (pintype "passive"))
    )
    (net (code "23") (name "KEY_C3") (class "Default")
      (node (ref "IC1") (pin "24") (pinfunction "(TCK)PC2_24") (pintype "bidirectional"))
      (node (ref "SV2") (pin "6") (pinfunction "6_6") (pintype "passive"))
    )
    (net (code "24") (name "KEY_C4") (class "Default")
      (node (ref "IC1") (pin "25") (pinfunction "(TMS)PC3_25") (pintype "bidirectional"))
      (node (ref "SV2") (pin "7") (pinfunction "7_7") (pintype "passive"))
    )
    (net (code "25") (name "KEY_R1") (class "Default")
      (node (ref "IC1") (pin "26") (pinfunction "(TDO)PC4_26") (pintype "bidirectional"))
      (node (ref "SV2") (pin "8") (pinfunction "8_8") (pintype "passive"))
    )
    (net (code "26") (name "KEY_R2") (class "Default")
      (node (ref "IC1") (pin "27") (pinfunction "(TDI)PC5_27") (pintype "bidirectional"))
      (node (ref "SV2") (pin "9") (pinfunction "9_9") (pintype "passive"))
    )
    (net (code "27") (name "KEY_R3") (class "Default")
      (node (ref "IC1") (pin "28") (pinfunction "(TOSC1)PC6_28") (pintype "bidirectional"))
      (node (ref "SV2") (pin "10") (pinfunction "10_10") (pintype "passive"))
    )
    (net (code "28") (name "KEY_R4") (class "Default")
      (node (ref "IC1") (pin "29") (pinfunction "(TOSC2)PC7_29") (pintype "bidirectional"))
      (node (ref "SV2") (pin "11") (pinfunction "11_11") (pintype "passive"))
    )
    (net (code "29") (name "LCD_A0") (class "Default")
      (node (ref "IC1") (pin "1") (pinfunction "(T0/XCK)PB0_1") (pintype "bidirectional"))
      (node (ref "R40") (pin "2") (pinfunction "2_2") (pintype "passive"))
    )
    (net (code "30") (name "LCD_A0_3V3") (class "Default")
      (node (ref "R40") (pin "1") (pinfunction "1_1") (pintype "passive"))
      (node (ref "R44") (pin "1") (pinfunction "1_1") (pintype "passive"))
      (node (ref "X1") (pin "7") (pinfunction "1_7") (pintype "passive"))
    )
    (net (code "31") (name "MISO") (class "Default")
      (node (ref "IC1") (pin "7") (pinfunction "(MISO)PB6_7") (pintype "bidirectional"))
      (node (ref "SV1") (pin "9") (pinfunction "9_9") (pintype "passive"))
    )
    (net (code "32") (name "MOSI") (class "Default")
      (node (ref "IC1") (pin "6") (pinfunction "(MOSI)PB5_6") (pintype "bidirectional"))
      (node (ref "IC2") (pin "5") (pinfunction "SDI_5") (pintype "input"))
      (node (ref "IC3") (pin "4") (pinfunction "SDI_4") (pintype "input"))
      (node (ref "R42") (pin "2") (pinfunction "2_2") (pintype "passive"))
      (node (ref "SV1") (pin "1") (pinfunction "1_1") (pintype "passive"))
    )
    (net (code "33") (name "MOSI_3V3") (class "Default")
      (node (ref "R42") (pin "1") (pinfunction "1_1") (pintype "passive"))
      (node (ref "R46") (pin "1") (pinfunction "1_1") (pintype "passive"))
      (node (ref "X1") (pin "11") (pinfunction "1_11") (pintype "passive"))
    )
    (net (code "34") (name "MV1") (class "Default")
      (node (ref "C21") (pin "1") (pinfunction "1_1") (pintype "passive"))
      (node (ref "X1") (pin "37") (pinfunction "1_37") (pintype "passive"))
    )
    (net (code "35") (name "MV2") (class "Default")
      (node (ref "C22") (pin "1") (pinfunction "1_1") (pintype "passive"))
      (node (ref "X1") (pin "43") (pinfunction "1_43") (pintype "passive"))
    )
    (net (code "36") (name "Net-(IC1-XTAL1)") (class "Default")
      (node (ref "C7") (pin "1") (pinfunction "1_1") (pintype "passive"))
      (node (ref "IC1") (pin "13") (pinfunction "XTAL1_13") (pintype "bidirectional"))
      (node (ref "Q8") (pin "1") (pinfunction "1_1") (pintype "passive"))
    )
    (net (code "37") (name "Net-(IC1-XTAL2)") (class "Default")
      (node (ref "C6") (pin "1") (pinfunction "1_1") (pintype "passive"))
      (node (ref "IC1") (pin "12") (pinfunction "XTAL2_12") (pintype "bidirectional"))
      (node (ref "Q8") (pin "2") (pinfunction "2_2") (pintype "passive"))
    )
    (net (code "38") (name "Net-(IC2-VOUTA)") (class "Default")
      (node (ref "IC2") (pin "14") (pinfunction "VOUTA_14") (pintype "output"))
      (node (ref "R1") (pin "1") (pinfunction "1_1") (pintype "passive"))
    )
    (net (code "39") (name "Net-(IC2-VOUTB)") (class "Default")
      (node (ref "IC2") (pin "10") (pinfunction "VOUTB_10") (pintype "output"))
      (node (ref "R9") (pin "1") (pinfunction "1_1") (pintype "passive"))
    )
    (net (code "40") (name "Net-(IC3-VOUT)") (class "Default")
      (node (ref "IC3") (pin "8") (pinfunction "VOUT_8") (pintype "output"))
      (node (ref "R17") (pin "1") (pinfunction "1_1") (pintype "passive"))
    )
    (net (code "41") (name "Net-(IC4A-+IN)") (class "Default")
      (node (ref "C2") (pin "2") (pinfunction "2_2") (pintype "passive"))
      (node (ref "IC4") (pin "3") (pinfunction "+IN_3") (pintype "input"))
      (node (ref "R1") (pin "2") (pinfunction "2_2") (pintype "passive"))
      (node (ref "R2") (pin "2") (pinfunction "2_2") (pintype "passive"))
    )
    (net (code "42") (name "Net-(IC4A--IN)") (class "Default")
      (node (ref "IC4") (pin "2") (pinfunction "-IN_2") (pintype "input"))
      (node (ref "R5") (pin "2") (pinfunction "2_2") (pintype "passive"))
      (node (ref "R6") (pin "1") (pinfunction "1_1") (pintype "passive"))
    )
    (net (code "43") (name "Net-(IC4A-OUT)") (class "Default")
      (node (ref "IC4") (pin "1") (pinfunction "OUT_1") (pintype "output"))
      (node (ref "IC4") (pin "5") (pinfunction "+IN_5") (pintype "input"))
      (node (ref "R6") (pin "2") (pinfunction "2_2") (pintype "passive"))
    )
    (net (code "44") (name "Net-(IC4B--IN)") (class "Default")
      (node (ref "IC4") (pin "6") (pinfunction "-IN_6") (pintype "input"))
      (node (ref "Q1") (pin "1") (pinfunction "E_1") (pintype "passive"))
      (node (ref "Q2") (pin "1") (pinfunction "E_1") (pintype "passive"))
      (node (ref "R7") (pin "2") (pinfunction "2_2") (pintype "passive"))
      (node (ref "R8") (pin "1") (pinfunction "1_1") (pintype "passive"))
    )
    (net (code "45") (name "Net-(IC4B-OUT)") (class "Default")
      (node (ref "IC4") (pin "7") (pinfunction "OUT_7") (pintype "output"))
      (node (ref "Q1") (pin "2") (pinfunction "B_2") (pintype "passive"))
      (node (ref "Q2") (pin "2") (pinfunction "B_2") (pintype "passive"))
      (node (ref "R7") (pin "1") (pinfunction "1_1") (pintype "passive"))
    )
    (net (code "46") (name "Net-(IC4C-+IN)") (class "Default")
      (node (ref "C3") (pin "2") (pinfunction "2_2") (pintype "passive"))
      (node (ref "IC4") (pin "10") (pinfunction "+IN_10") (pintype "input"))
      (node (ref "R10") (pin "2") (pinfunction "2_2") (pintype "passive"))
      (node (ref "R9") (pin "2") (pinfunction "2_2") (pintype "passive"))
    )
    (net (code "47") (name "Net-(IC4C--IN)") (class "Default")
      (node (ref "IC4") (pin "9") (pinfunction "-IN_9") (pintype "input"))
      (node (ref "R13") (pin "2") (pinfunction "2_2") (pintype "passive"))
      (node (ref "R14") (pin "1") (pinfunction "1_1") (pintype "passive"))
    )
    (net (code "48") (name "Net-(IC4C-OUT)") (class "Default")
      (node (ref "IC4") (pin "12") (pinfunction "+IN_12") (pintype "input"))
      (node (ref "IC4") (pin "8") (pinfunction "OUT_8") (pintype "output"))
      (node (ref "R14") (pin "2") (pinfunction "2_2") (pintype "passive"))
    )
    (net (code "49") (name "Net-(IC4D--IN)") (class "Default")
      (node (ref "IC4") (pin "13") (pinfunction "-IN_13") (pintype "input"))
      (node (ref "Q3") (pin "1") (pinfunction "E_1") (pintype "passive"))
      (node (ref "Q4") (pin "1") (pinfunction "E_1") (pintype "passive"))
      (node (ref "R15") (pin "2") (pinfunction "2_2") (pintype "passive"))
      (node (ref "R16") (pin "1") (pinfunction "1_1") (pintype "passive"))
    )
    (net (code "50") (name "Net-(IC4D-OUT)") (class "Default")
      (node (ref "IC4") (pin "14") (pinfunction "OUT_14") (pintype "output"))
      (node (ref "Q3") (pin "2") (pinfunction "B_2") (pintype "passive"))
      (node (ref "Q4") (pin "2") (pinfunction "B_2") (pintype "passive"))
      (node (ref "R15") (pin "1") (pinfunction "1_1") (pintype "passive"))
    )
    (net (code "51") (name "Net-(IC5A-+IN)") (class "Default")
      (node (ref "C5") (pin "2") (pinfunction "2_2") (pintype "passive"))
      (node (ref "IC5") (pin "3") (pinfunction "+IN_3") (pintype "input"))
      (node (ref "R17") (pin "2") (pinfunction "2_2") (pintype "passive"))
    )
    (net (code "52") (name "Net-(IC5A--IN)") (class "Default")
      (node (ref "IC5") (pin "2") (pinfunction "-IN_2") (pintype "input"))
      (node (ref "R18") (pin "2") (pinfunction "2_2") (pintype "passive"))
      (node (ref "R19") (pin "1") (pinfunction "1_1") (pintype "passive"))
    )
    (net (code "53") (name "Net-(IC5A-OUT)") (class "Default")
      (node (ref "IC5") (pin "1") (pinfunction "OUT_1") (pintype "output"))
      (node (ref "IC5") (pin "5") (pinfunction "+IN_5") (pintype "input"))
      (node (ref "R19") (pin "2") (pinfunction "2_2") (pintype "passive"))
    )
    (net (code "54") (name "Net-(IC5B--IN)") (class "Default")
      (node (ref "IC5") (pin "6") (pinfunction "-IN_6") (pintype "input"))
      (node (ref "Q5") (pin "G") (pinfunction "E_G") (pintype "passive"))
      (node (ref "R22") (pin "1") (pinfunction "1_1") (pintype "passive"))
      (node (ref "R23") (pin "2") (pinfunction "2_2") (pintype "passive"))
    )
    (net (code "55") (name "Net-(IC5B-OUT)") (class "Default")
      (node (ref "IC5") (pin "7") (pinfunction "OUT_7") (pintype "output"))
      (node (ref "Q6") (pin "2") (pinfunction "B_2") (pintype "passive"))
    )
    (net (code "56") (name "Net-(IC5C-+IN)") (class "Default")
      (node (ref "IC5") (pin "10") (pinfunction "+IN_10") (pintype "input"))
      (node (ref "R21") (pin "1") (pinfunction "1_1") (pintype "passive"))
      (node (ref "R22") (pin "2") (pinfunction "2_2") (pintype "passive"))
    )
    (net (code "57") (name "Net-(IC5C--IN)") (class "Default")
      (node (ref "IC5") (pin "9") (pinfunction "-IN_9") (pintype "input"))
      (node (ref "Q7") (pin "E") (pinfunction "E_E") (pintype "passive"))
      (node (ref "R23") (pin "1") (pinfunction "1_1") (pintype "passive"))
    )
    (net (code "58") (name "Net-(IC5C-OUT)") (class "Default")
      (node (ref "IC5") (pin "8") (pinfunction "OUT_8") (pintype "output"))
      (node (ref "Q7") (pin "B") (pinfunction "B_B") (pintype "passive"))
    )
    (net (code "59") (name "Net-(IC5D--IN)") (class "Default")
      (node (ref "IC5") (pin "13") (pinfunction "-IN_13") (pintype "input"))
      (node (ref "R27") (pin "1") (pinfunction "1_1") (pintype "passive"))
      (node (ref "R28") (pin "2") (pinfunction "2_2") (pintype "passive"))
    )
    (net (code "60") (name "Net-(IC6-3V3OUT)") (class "Default")
      (node (ref "C11") (pin "1") (pinfunction "1_1") (pintype "passive"))
      (node (ref "IC6") (pin "17") (pinfunction "3V3OUT_17") (pintype "output"))
    )
    (net (code "61") (name "Net-(IC6-CBUS0)") (class "Default")
      (node (ref "IC6") (pin "23") (pinfunction "CBUS0_23") (pintype "bidirectional"))
      (node (ref "LED1") (pin "4") (pinfunction "C_4") (pintype "passive"))
    )
    (net (code "62") (name "Net-(IC6-CBUS1)") (class "Default")
      (node (ref "IC6") (pin "22") (pinfunction "CBUS1_22") (pintype "bidirectional"))
      (node (ref "LED1") (pin "1") (pinfunction "C_1") (pintype "passive"))
    )
    (net (code "63") (name "Net-(IC6-USBDM)") (class "Default")
      (node (ref "IC6") (pin "16") (pinfunction "USBDM_16") (pintype "bidirectional"))
      (node (ref "X3") (pin "2") (pinfunction "2_2") (pintype "passive"))
    )
    (net (code "64") (name "Net-(IC6-USBDP)") (class "Default")
      (node (ref "IC6") (pin "15") (pinfunction "USBDP_15") (pintype "bidirectional"))
      (node (ref "X3") (pin "3") (pinfunction "3_3") (pintype "passive"))
    )
    (net (code "65") (name "Net-(LED1A-A)") (class "Default")
      (node (ref "LED1") (pin "2") (pinfunction "A_2") (pintype "passive"))
      (node (ref "R32") (pin "1") (pinfunction "1_1") (pintype "passive"))
    )
    (net (code "66") (name "Net-(LED1B-A)") (class "Default")
      (node (ref "LED1") (pin "3") (pinfunction "A_3") (pintype "passive"))
      (node (ref "R31") (pin "1") (pinfunction "1_1") (pintype "passive"))
    )
    (net (code "67") (name "Net-(LED2-PadA)") (class "Default")
      (node (ref "LED2") (pin "A") (pinfunction "A_A") (pintype "passive"))
      (node (ref "R33") (pin "1") (pinfunction "1_1") (pintype "passive"))
    )
    (net (code "68") (name "Net-(OUT1-P)") (class "Default")
      (node (ref "OUT1") (pin "1") (pinfunction "P_1") (pintype "passive"))
      (node (ref "R8") (pin "2") (pinfunction "2_2") (pintype "passive"))
    )
    (net (code "69") (name "Net-(OUT2-P)") (class "Default")
      (node (ref "OUT2") (pin "1") (pinfunction "P_1") (pintype "passive"))
      (node (ref "R16") (pin "2") (pinfunction "2_2") (pintype "passive"))
    )
    (net (code "70") (name "Net-(OUT3-P)") (class "Default")
      (node (ref "OUT3") (pin "1") (pinfunction "P_1") (pintype "passive"))
      (node (ref "R21") (pin "2") (pinfunction "2_2") (pintype "passive"))
      (node (ref "R25") (pin "2") (pinfunction "2_2") (pintype "passive"))
    )
    (net (code "71") (name "Net-(Q5-B)") (class "Default")
      (node (ref "Q5") (pin "T1") (pinfunction "B_T1") (pintype "passive"))
      (node (ref "Q6") (pin "1") (pinfunction "E_1") (pintype "passive"))
    )
    (net (code "72") (name "Net-(R3-Pad2)") (class "Default")
      (node (ref "R3") (pin "2") (pinfunction "2_2") (pintype "passive"))
      (node (ref "R4") (pin "2") (pinfunction "2_2") (pintype "passive"))
      (node (ref "R5") (pin "1") (pinfunction "1_1") (pintype "passive"))
    )
    (net (code "73") (name "Net-(R11-Pad2)") (class "Default")
      (node (ref "R11") (pin "2") (pinfunction "2_2") (pintype "passive"))
      (node (ref "R12") (pin "2") (pinfunction "2_2") (pintype "passive"))
      (node (ref "R13") (pin "1") (pinfunction "1_1") (pintype "passive"))
    )
    (net (code "74") (name "PS_CUR") (class "Default")
      (node (ref "IC1") (pin "40") (pinfunction "(ADC0)PA0_40") (pintype "bidirectional"))
      (node (ref "Q7") (pin "C") (pinfunction "C_C") (pintype "passive"))
      (node (ref "R24") (pin "2") (pinfunction "2_2") (pintype "passive"))
    )
    (net (code "75") (name "PS_VOLT") (class "Default")
      (node (ref "IC1") (pin "39") (pinfunction "(ADC1)PA1_39") (pintype "bidirectional"))
      (node (ref "R25") (pin "1") (pinfunction "1_1") (pintype "passive"))
      (node (ref "R26") (pin "2") (pinfunction "2_2") (pintype "passive"))
    )
    (net (code "76") (name "RST") (class "Default")
      (node (ref "IC1") (pin "9") (pinfunction "RESET_9") (pintype "input"))
      (node (ref "SV1") (pin "5") (pinfunction "5_5") (pintype "passive"))
    )
    (net (code "77") (name "SCK") (class "Default")
      (node (ref "IC1") (pin "8") (pinfunction "(SCK)PB7_8") (pintype "bidirectional"))
      (node (ref "IC2") (pin "4") (pinfunction "SCK_4") (pintype "input"))
      (node (ref "IC3") (pin "3") (pinfunction "SCK_3") (pintype "input"))
      (node (ref "R41") (pin "2") (pinfunction "2_2") (pintype "passive"))
      (node (ref "SV1") (pin "7") (pinfunction "7_7") (pintype "passive"))
    )
    (net (code "78") (name "SCK_3V3") (class "Default")
      (node (ref "R41") (pin "1") (pinfunction "1_1") (pintype "passive"))
      (node (ref "R45") (pin "1") (pinfunction "1_1") (pintype "passive"))
      (node (ref "X1") (pin "9") (pinfunction "1_9") (pintype "passive"))
    )
    (net (code "79") (name "USB_RX") (class "Default")
      (node (ref "IC1") (pin "14") (pinfunction "(RXD)PD0_14") (pintype "bidirectional"))
      (node (ref "IC6") (pin "1") (pinfunction "TXD_1") (pintype "output"))
    )
    (net (code "80") (name "USB_TX") (class "Default")
      (node (ref "IC1") (pin "15") (pinfunction "(TXD)PD1_15") (pintype "bidirectional"))
      (node (ref "IC6") (pin "5") (pinfunction "RXD_5") (pintype "input"))
    )
    (net (code "81") (name "V1") (class "Default")
      (node (ref "C17") (pin "1") (pinfunction "1_1") (pintype "passive"))
      (node (ref "X1") (pin "29") (pinfunction "1_29") (pintype "passive"))
    )
    (net (code "82") (name "V2") (class "Default")
      (node (ref "C18") (pin "1") (pinfunction "1_1") (pintype "passive"))
      (node (ref "X1") (pin "31") (pinfunction "1_31") (pintype "passive"))
    )
    (net (code "83") (name "V3") (class "Default")
      (node (ref "C19") (pin "1") (pinfunction "1_1") (pintype "passive"))
      (node (ref "X1") (pin "33") (pinfunction "1_33") (pintype "passive"))
    )
    (net (code "84") (name "VC") (class "Default")
      (node (ref "C20") (pin "1") (pinfunction "1_1") (pintype "passive"))
      (node (ref "X1") (pin "35") (pinfunction "1_35") (pintype "passive"))
    )
    (net (code "85") (name "VOUT") (class "Default")
      (node (ref "C13") (pin "1") (pinfunction "1_1") (pintype "passive"))
      (node (ref "X1") (pin "17") (pinfunction "1_17") (pintype "passive"))
    )
    (net (code "86") (name "unconnected-(IC1-(OC2)PD7-Pad21)") (class "Default")
      (node (ref "IC1") (pin "21") (pinfunction "(OC2)PD7_21") (pintype "bidirectional"))
    )
    (net (code "87") (name "unconnected-(IC6-CBUS2-Pad13)") (class "Default")
      (node (ref "IC6") (pin "13") (pinfunction "CBUS2_13") (pintype "bidirectional"))
    )
    (net (code "88") (name "unconnected-(IC6-CBUS3-Pad14)") (class "Default")
      (node (ref "IC6") (pin "14") (pinfunction "CBUS3_14") (pintype "bidirectional"))
    )
    (net (code "89") (name "unconnected-(IC6-CBUS4-Pad12)") (class "Default")
      (node (ref "IC6") (pin "12") (pinfunction "CBUS4_12") (pintype "bidirectional"))
    )
    (net (code "90") (name "unconnected-(IC6-OSCI-Pad27)") (class "Default")
      (node (ref "IC6") (pin "27") (pinfunction "OSCI_27") (pintype "input"))
    )
    (net (code "91") (name "unconnected-(IC6-OSCO-Pad28)") (class "Default")
      (node (ref "IC6") (pin "28") (pinfunction "OSCO_28") (pintype "output"))
    )
    (net (code "92") (name "unconnected-(IC6-~{CTS}-Pad11)") (class "Default")
      (node (ref "IC6") (pin "11") (pinfunction "~{CTS}_11") (pintype "input"))
    )
    (net (code "93") (name "unconnected-(IC6-~{DCD}-Pad10)") (class "Default")
      (node (ref "IC6") (pin "10") (pinfunction "~{DCD}_10") (pintype "input"))
    )
    (net (code "94") (name "unconnected-(IC6-~{DSR}-Pad9)") (class "Default")
      (node (ref "IC6") (pin "9") (pinfunction "~{DSR}_9") (pintype "input"))
    )
    (net (code "95") (name "unconnected-(IC6-~{DTR}-Pad2)") (class "Default")
      (node (ref "IC6") (pin "2") (pinfunction "~{DTR}_2") (pintype "output"))
    )
    (net (code "96") (name "unconnected-(IC6-~{RESET}-Pad19)") (class "Default")
      (node (ref "IC6") (pin "19") (pinfunction "~{RESET}_19") (pintype "input"))
    )
    (net (code "97") (name "unconnected-(IC6-~{RI}-Pad6)") (class "Default")
      (node (ref "IC6") (pin "6") (pinfunction "~{RI}_6") (pintype "input"))
    )
    (net (code "98") (name "unconnected-(IC6-~{RTS}-Pad3)") (class "Default")
      (node (ref "IC6") (pin "3") (pinfunction "~{RTS}_3") (pintype "output"))
    )
    (net (code "99") (name "unconnected-(SV1-Pad3)") (class "Default")
      (node (ref "SV1") (pin "3") (pinfunction "3_3") (pintype "passive"))
    )
    (net (code "100") (name "unconnected-(SV2-Pad14)") (class "Default")
      (node (ref "SV2") (pin "14") (pinfunction "14_14") (pintype "passive"))
    )
    (net (code "101") (name "unconnected-(U$2-D+(B)-PadP$6)") (class "Default")
      (node (ref "U$2") (pin "P$6") (pinfunction "D+(B)_P$6") (pintype "bidirectional"))
    )
    (net (code "102") (name "unconnected-(U$2-D+-PadP$8)") (class "Default")
      (node (ref "U$2") (pin "P$8") (pinfunction "D+_P$8") (pintype "bidirectional"))
    )
    (net (code "103") (name "unconnected-(U$2-D-(B)-PadP$5)") (class "Default")
      (node (ref "U$2") (pin "P$5") (pinfunction "D-(B)_P$5") (pintype "bidirectional"))
    )
    (net (code "104") (name "unconnected-(U$2-D--PadP$7)") (class "Default")
      (node (ref "U$2") (pin "P$7") (pinfunction "D-_P$7") (pintype "bidirectional"))
    )
    (net (code "105") (name "unconnected-(X1AB-1-Pad34)") (class "Default")
      (node (ref "X1") (pin "34") (pinfunction "1_34") (pintype "passive"))
    )
    (net (code "106") (name "unconnected-(X1AD-1-Pad36)") (class "Default")
      (node (ref "X1") (pin "36") (pinfunction "1_36") (pintype "passive"))
    )
    (net (code "107") (name "unconnected-(X1AF-1-Pad38)") (class "Default")
      (node (ref "X1") (pin "38") (pinfunction "1_38") (pintype "passive"))
    )
    (net (code "108") (name "unconnected-(X1AG-1-Pad39)") (class "Default")
      (node (ref "X1") (pin "39") (pinfunction "1_39") (pintype "passive"))
    )
    (net (code "109") (name "unconnected-(X1AH-1-Pad4)") (class "Default")
      (node (ref "X1") (pin "4") (pinfunction "1_4") (pintype "passive"))
    )
    (net (code "110") (name "unconnected-(X1AI-1-Pad40)") (class "Default")
      (node (ref "X1") (pin "40") (pinfunction "1_40") (pintype "passive"))
    )
    (net (code "111") (name "unconnected-(X1AJ-1-Pad41)") (class "Default")
      (node (ref "X1") (pin "41") (pinfunction "1_41") (pintype "passive"))
    )
    (net (code "112") (name "unconnected-(X1AK-1-Pad42)") (class "Default")
      (node (ref "X1") (pin "42") (pinfunction "1_42") (pintype "passive"))
    )
    (net (code "113") (name "unconnected-(X1AM-1-Pad44)") (class "Default")
      (node (ref "X1") (pin "44") (pinfunction "1_44") (pintype "passive"))
    )
    (net (code "114") (name "unconnected-(X1AN-1-Pad45)") (class "Default")
      (node (ref "X1") (pin "45") (pinfunction "1_45") (pintype "passive"))
    )
    (net (code "115") (name "unconnected-(X1AO-1-Pad5)") (class "Default")
      (node (ref "X1") (pin "5") (pinfunction "1_5") (pintype "passive"))
    )
    (net (code "116") (name "unconnected-(X1AP-1-Pad6)") (class "Default")
      (node (ref "X1") (pin "6") (pinfunction "1_6") (pintype "passive"))
    )
    (net (code "117") (name "unconnected-(X1AR-1-Pad8)") (class "Default")
      (node (ref "X1") (pin "8") (pinfunction "1_8") (pintype "passive"))
    )
    (net (code "118") (name "unconnected-(X1B-1-Pad10)") (class "Default")
      (node (ref "X1") (pin "10") (pinfunction "1_10") (pintype "passive"))
    )
    (net (code "119") (name "unconnected-(X1D-1-Pad12)") (class "Default")
      (node (ref "X1") (pin "12") (pinfunction "1_12") (pintype "passive"))
    )
    (net (code "120") (name "unconnected-(X1F-1-Pad14)") (class "Default")
      (node (ref "X1") (pin "14") (pinfunction "1_14") (pintype "passive"))
    )
    (net (code "121") (name "unconnected-(X1H-1-Pad16)") (class "Default")
      (node (ref "X1") (pin "16") (pinfunction "1_16") (pintype "passive"))
    )
    (net (code "122") (name "unconnected-(X1J-1-Pad18)") (class "Default")
      (node (ref "X1") (pin "18") (pinfunction "1_18") (pintype "passive"))
    )
    (net (code "123") (name "unconnected-(X1L-1-Pad2)") (class "Default")
      (node (ref "X1") (pin "2") (pinfunction "1_2") (pintype "passive"))
    )
    (net (code "124") (name "unconnected-(X1M-1-Pad20)") (class "Default")
      (node (ref "X1") (pin "20") (pinfunction "1_20") (pintype "passive"))
    )
    (net (code "125") (name "unconnected-(X1O-1-Pad22)") (class "Default")
      (node (ref "X1") (pin "22") (pinfunction "1_22") (pintype "passive"))
    )
    (net (code "126") (name "unconnected-(X1Q-1-Pad24)") (class "Default")
      (node (ref "X1") (pin "24") (pinfunction "1_24") (pintype "passive"))
    )
    (net (code "127") (name "unconnected-(X1S-1-Pad26)") (class "Default")
      (node (ref "X1") (pin "26") (pinfunction "1_26") (pintype "passive"))
    )
    (net (code "128") (name "unconnected-(X1U-1-Pad28)") (class "Default")
      (node (ref "X1") (pin "28") (pinfunction "1_28") (pintype "passive"))
    )
    (net (code "129") (name "unconnected-(X1X-1-Pad30)") (class "Default")
      (node (ref "X1") (pin "30") (pinfunction "1_30") (pintype "passive"))
    )
    (net (code "130") (name "unconnected-(X1Z-1-Pad32)") (class "Default")
      (node (ref "X1") (pin "32") (pinfunction "1_32") (pintype "passive"))
    )
    (net (code "131") (name "~{DDS_CS}") (class "Default")
      (node (ref "IC1") (pin "4") (pinfunction "(AIN1/OC0)PB3_4") (pintype "bidirectional"))
      (node (ref "IC2") (pin "3") (pinfunction "~{CS}_3") (pintype "input"))
    )
    (net (code "132") (name "~{DDS_LDAC}") (class "Default")
      (node (ref "IC1") (pin "3") (pinfunction "(AIN0/INT2)PB2_3") (pintype "bidirectional"))
      (node (ref "IC2") (pin "8") (pinfunction "~{LDAC}_8") (pintype "input"))
    )
    (net (code "133") (name "~{LCD_CS_3V3}") (class "Default")
      (node (ref "R39") (pin "1") (pinfunction "1_1") (pintype "passive"))
      (node (ref "R43") (pin "1") (pinfunction "1_1") (pintype "passive"))
      (node (ref "X1") (pin "3") (pinfunction "1_3") (pintype "passive"))
    )
    (net (code "134") (name "~{LCD_CS}") (class "Default")
      (node (ref "IC1") (pin "2") (pinfunction "(T1)PB1_2") (pintype "bidirectional"))
      (node (ref "R39") (pin "2") (pinfunction "2_2") (pintype "passive"))
    )
    (net (code "135") (name "~{PS_CS}") (class "Default")
      (node (ref "IC1") (pin "5") (pinfunction "(SS)PB4_5") (pintype "bidirectional"))
      (node (ref "IC3") (pin "2") (pinfunction "~{CS}_2") (pintype "input"))
    )
  )
)
